# Power.net
KiCad netlist of a schematic drawn in Altium Designer
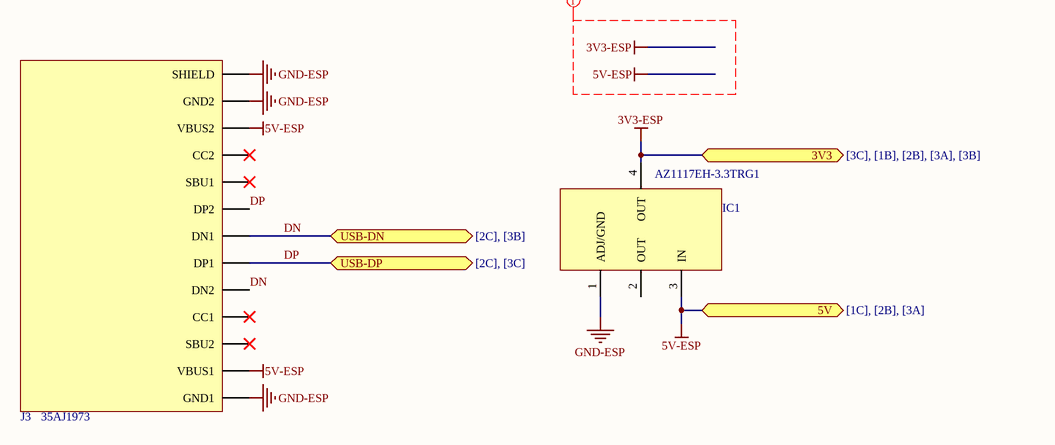
[diagram p0: Power.SchDoc]

(export (version "E")
  (design (tool "Eeschema 10.0.6"))
  (components
    (comp (ref "IC1")
      (value "Linear Voltage Regulator IC Positive Fixed 1 Output 1A SOT-223-3")
      (footprint "IC:SOT-223-3-DI")
      (description "Linear Voltage Regulator IC 1 Output 1A SOT-223")
      (fields
        (field (name "MF") "Diodes Inc.")
        (field (name "MP") "AZ1117EH-3.3TRG1")
        (field (name "DESIGNER") "TVBac")
      )
      (libsource (lib "IC") (part "LDO; 3V3; 1A; SMD; AZ1117EH-3.3TRG1"))
    )
    (comp (ref "J3")
      (value "USB-C (USB TYPE-C) USB 2.0 Receptacle Connector 24 (16+8 Dummy) Position Surface Mount, Right Angle; Through Hole")
      (footprint "TYPE-C-HOR-RECEPTACLE-24PIN-MOLEX")
      (description "USB Connector, 16 Contact(s), Female, Right Angle, Surface Mount Terminal, Locking, Receptacle")
      (fields
        (field (name "SUPPLIER PART NUMBER") "35AJ1973")
        (field (name "MANUFACTURER") "Molex")
        (field (name "MANUFACTURER PART NUMBER") "217179-0001")
        (field (name "DESIGNER") "TVBac")
      )
      (libsource (lib "Socket") (part "Type-C; USB; HOR; RECEPTACLE;  24PIN; 217179-0001"))
    )
  )
  (nets
    (net (code "1") (name "/DN") (class "Default")
      (node (ref "J3") (pin "A7") (pinfunction "DN1_A7") (pintype "passive"))
      (node (ref "J3") (pin "B7") (pinfunction "DN2_B7") (pintype "passive"))
    )
    (net (code "2") (name "/DP") (class "Default")
      (node (ref "J3") (pin "A6") (pinfunction "DP1_A6") (pintype "passive"))
      (node (ref "J3") (pin "B6") (pinfunction "DP2_B6") (pintype "passive"))
    )
    (net (code "3") (name "3V3-ESP") (class "Default")
      (node (ref "IC1") (pin "4") (pinfunction "OUT_4") (pintype "passive"))
    )
    (net (code "4") (name "5V-ESP") (class "Default")
      (node (ref "IC1") (pin "3") (pinfunction "IN_3") (pintype "passive"))
      (node (ref "J3") (pin "A4B9") (pinfunction "VBUS1_A4B9") (pintype "passive"))
      (node (ref "J3") (pin "B4A9") (pinfunction "VBUS2_B4A9") (pintype "passive"))
    )
    (net (code "5") (name "GND-ESP") (class "Default")
      (node (ref "IC1") (pin "1") (pinfunction "ADJ/GND_1") (pintype "passive"))
      (node (ref "J3") (pin "A1B12") (pinfunction "GND1_A1B12") (pintype "passive"))
      (node (ref "J3") (pin "B1A12") (pinfunction "GND2_B1A12") (pintype "passive"))
      (node (ref "J3") (pin "SHIELD") (pinfunction "SHIELD_SHIELD") (pintype "passive"))
    )
    (net (code "6") (name "unconnected-(IC1-OUT-Pad2)") (class "Default")
      (node (ref "IC1") (pin "2") (pinfunction "OUT_2") (pintype "passive"))
    )
    (net (code "7") (name "unconnected-(J3-CC1-PadA5)") (class "Default")
      (node (ref "J3") (pin "A5") (pinfunction "CC1_A5") (pintype "passive+no_connect"))
    )
    (net (code "8") (name "unconnected-(J3-CC2-PadB5)") (class "Default")
      (node (ref "J3") (pin "B5") (pinfunction "CC2_B5") (pintype "passive+no_connect"))
    )
    (net (code "9") (name "unconnected-(J3-SBU1-PadA8)") (class "Default")
      (node (ref "J3") (pin "A8") (pinfunction "SBU1_A8") (pintype "passive+no_connect"))
    )
    (net (code "10") (name "unconnected-(J3-SBU2-PadB8)") (class "Default")
      (node (ref "J3") (pin "B8") (pinfunction "SBU2_B8") (pintype "passive+no_connect"))
    )
  )
)
